# RELE_TTL.net
KiCad netlist of a schematic drawn in EAGLE
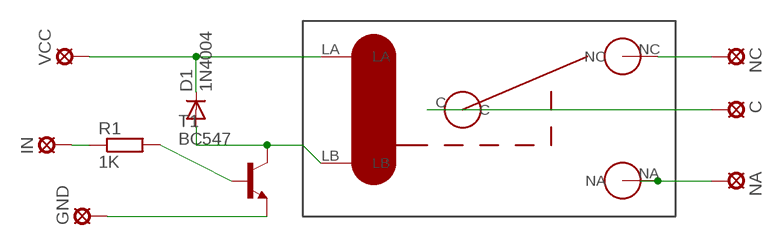
[diagram p0: schematic, sheet 1]

(export (version "E")
  (design (tool "Eeschema 10.0.6"))
  (components
    (comp (ref "C")
      (value "LSP10")
      (footprint "eagle-import:LSP10")
      (libsource (lib "eagle-import") (part "LSP10"))
    )
    (comp (ref "D1")
      (value "1N4004")
      (footprint "eagle-import:DO41-10")
      (libsource (lib "eagle-import") (part "1N4004"))
    )
    (comp (ref "GND")
      (value "LSP10")
      (footprint "eagle-import:LSP10")
      (libsource (lib "eagle-import") (part "LSP10"))
    )
    (comp (ref "IN")
      (value "LSP10")
      (footprint "eagle-import:LSP10")
      (libsource (lib "eagle-import") (part "LSP10"))
    )
    (comp (ref "NA")
      (value "LSP10")
      (footprint "eagle-import:LSP10")
      (libsource (lib "eagle-import") (part "LSP10"))
    )
    (comp (ref "NC")
      (value "LSP10")
      (footprint "eagle-import:LSP10")
      (libsource (lib "eagle-import") (part "LSP10"))
    )
    (comp (ref "R1")
      (value "1K")
      (footprint "eagle-import:0207_2V")
      (libsource (lib "eagle-import") (part "R-EU_0207/2V"))
    )
    (comp (ref "RL1")
      (value "RELE")
      (footprint "eagle-import:RELE_1")
      (libsource (lib "eagle-import") (part "RELE"))
    )
    (comp (ref "T1")
      (value "BC547")
      (footprint "eagle-import:TO92")
      (libsource (lib "eagle-import") (part "BC547"))
    )
    (comp (ref "VCC")
      (value "LSP10")
      (footprint "eagle-import:LSP10")
      (libsource (lib "eagle-import") (part "LSP10"))
    )
  )
  (nets
    (net (code "1") (name "Net-(C-PadMP)") (class "Default")
      (node (ref "C") (pin "MP") (pinfunction "MP_MP") (pintype "passive"))
      (node (ref "RL1") (pin "C") (pinfunction "C_C") (pintype "bidirectional"))
    )
    (net (code "2") (name "Net-(D1-PadC)") (class "Default")
      (node (ref "D1") (pin "C") (pinfunction "C_C") (pintype "passive"))
      (node (ref "RL1") (pin "LA") (pinfunction "LA_LA") (pintype "bidirectional"))
      (node (ref "VCC") (pin "MP") (pinfunction "MP_MP") (pintype "passive"))
    )
    (net (code "3") (name "Net-(IN-PadMP)") (class "Default")
      (node (ref "IN") (pin "MP") (pinfunction "MP_MP") (pintype "passive"))
      (node (ref "R1") (pin "1") (pinfunction "1_1") (pintype "passive"))
    )
    (net (code "4") (name "Net-(NA-PadMP)") (class "Default")
      (node (ref "NA") (pin "MP") (pinfunction "MP_MP") (pintype "passive"))
      (node (ref "RL1") (pin "NA") (pinfunction "NA_NA") (pintype "bidirectional"))
    )
    (net (code "5") (name "Net-(NC-PadMP)") (class "Default")
      (node (ref "NC") (pin "MP") (pinfunction "MP_MP") (pintype "passive"))
      (node (ref "RL1") (pin "NC") (pinfunction "NC_NC") (pintype "bidirectional"))
    )
    (net (code "6") (name "Net-(T1-B)") (class "Default")
      (node (ref "R1") (pin "2") (pinfunction "2_2") (pintype "passive"))
      (node (ref "T1") (pin "2") (pinfunction "B_2") (pintype "passive"))
    )
    (net (code "7") (name "Net-(T1-C)") (class "Default")
      (node (ref "D1") (pin "A") (pinfunction "A_A") (pintype "passive"))
      (node (ref "RL1") (pin "LB") (pinfunction "LB_LB") (pintype "bidirectional"))
      (node (ref "T1") (pin "3") (pinfunction "C_3") (pintype "passive"))
    )
    (net (code "8") (name "Net-(T1-E)") (class "Default")
      (node (ref "GND") (pin "MP") (pinfunction "MP_MP") (pintype "passive"))
      (node (ref "T1") (pin "1") (pinfunction "E_1") (pintype "passive"))
    )
  )
)
